# LEDMATRIX.net
KiCad netlist of a schematic drawn in Altium Designer
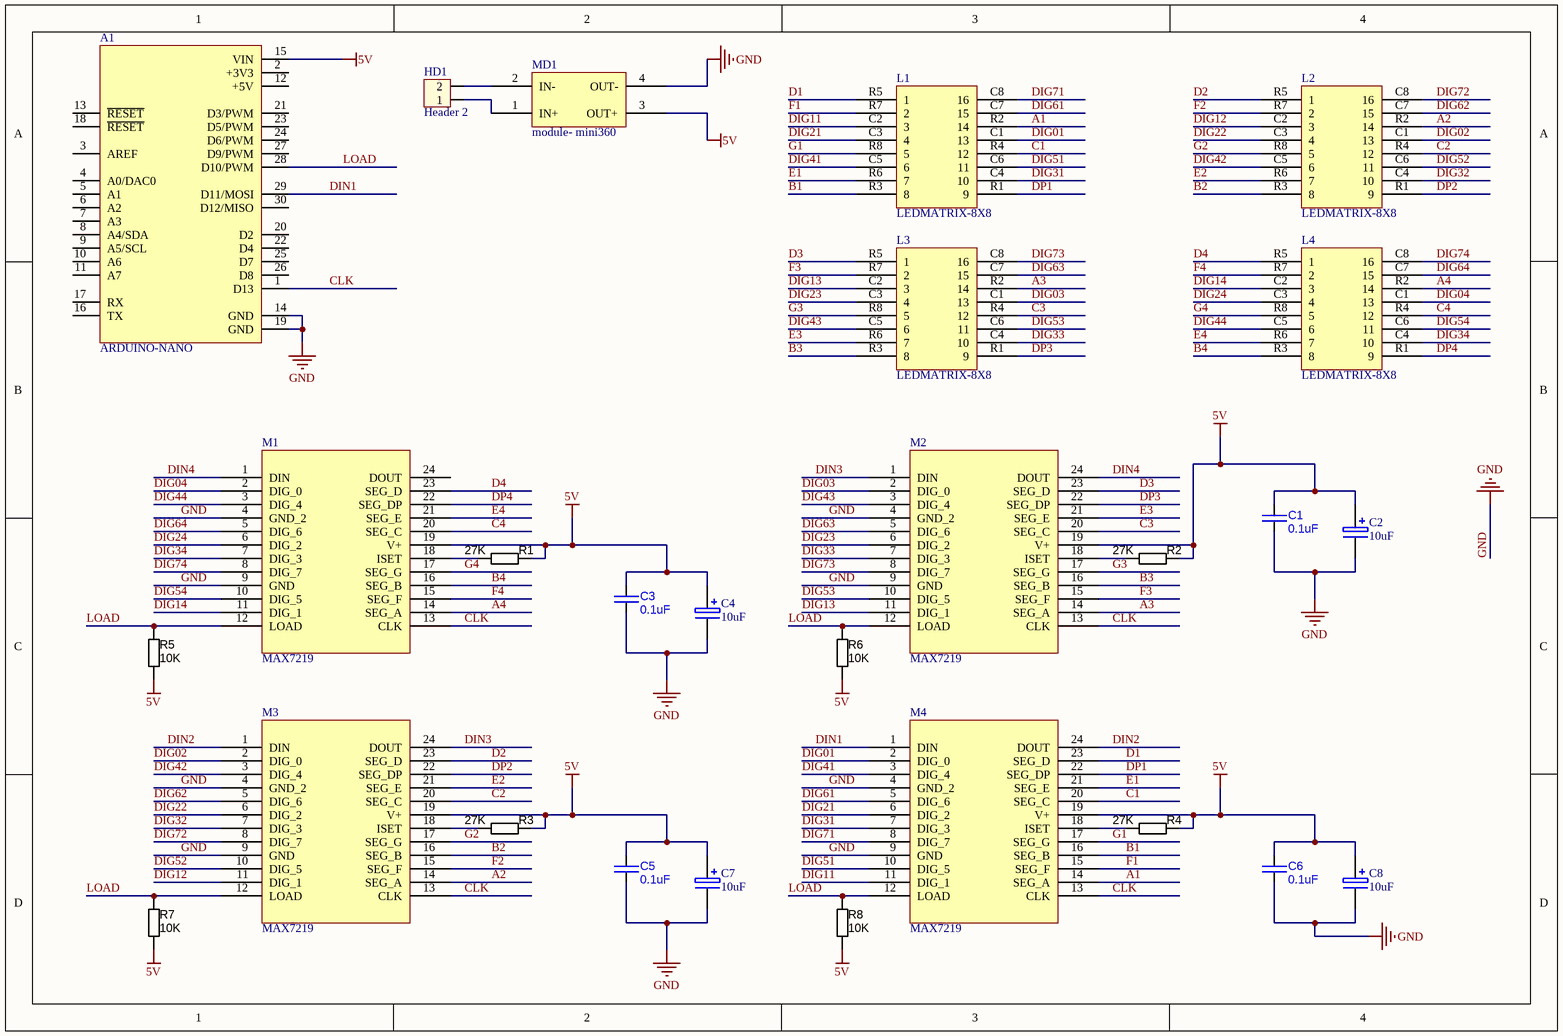
[diagram p0: LEDMATRIX.SchDoc]

(export (version "E")
  (design (tool "Eeschema 10.0.6"))
  (components
    (comp (ref "A1")
      (value "ARDUINO-NANO")
      (footprint "ARDUINO-NANO")
      (libsource (lib "ledmatrix") (part "ARDUINO-NANO"))
    )
    (comp (ref "C1")
      (value "0.1uF")
      (footprint "CAPC2012X135N")
      (description "Capacitor SMD Cer 1.8nF 10% 50V X7R 0805")
      (fields (field (name "TOLERANCE") "±10%") (field (name "Comment") "approved sub OK"))
      (libsource (lib "My library altium") (part "CAP C_0805"))
    )
    (comp (ref "C2")
      (value "10uF")
      (footprint "CP1/2")
      (description "Cap")
      (libsource (lib "My library altium") (part "CAP hoa"))
    )
    (comp (ref "C3")
      (value "0.1uF")
      (footprint "CAPC2012X135N")
      (description "Capacitor SMD Cer 1.8nF 10% 50V X7R 0805")
      (fields (field (name "TOLERANCE") "±10%") (field (name "Comment") "approved sub OK"))
      (libsource (lib "My library altium") (part "CAP C_0805"))
    )
    (comp (ref "C4")
      (value "10uF")
      (footprint "CP1/2")
      (description "Cap")
      (libsource (lib "My library altium") (part "CAP hoa"))
    )
    (comp (ref "C5")
      (value "0.1uF")
      (footprint "CAPC2012X135N")
      (description "Capacitor SMD Cer 1.8nF 10% 50V X7R 0805")
      (fields (field (name "TOLERANCE") "±10%") (field (name "Comment") "approved sub OK"))
      (libsource (lib "My library altium") (part "CAP C_0805"))
    )
    (comp (ref "C6")
      (value "0.1uF")
      (footprint "CAPC2012X135N")
      (description "Capacitor SMD Cer 1.8nF 10% 50V X7R 0805")
      (fields (field (name "TOLERANCE") "±10%") (field (name "Comment") "approved sub OK"))
      (libsource (lib "My library altium") (part "CAP C_0805"))
    )
    (comp (ref "C7")
      (value "10uF")
      (footprint "CP1/2")
      (description "Cap")
      (libsource (lib "My library altium") (part "CAP hoa"))
    )
    (comp (ref "C8")
      (value "10uF")
      (footprint "CP1/2")
      (description "Cap")
      (libsource (lib "My library altium") (part "CAP hoa"))
    )
    (comp (ref "HD1")
      (value "Header 2")
      (footprint "HED2")
      (description "Header 2 (Green)")
      (libsource (lib "My library altium") (part "Header 2"))
    )
    (comp (ref "L1")
      (value "LEDMATRIX-8X8")
      (footprint "LEDMATRIX_8X8")
      (libsource (lib "ledmatrix") (part "LEDMATRIX-8X8"))
    )
    (comp (ref "L2")
      (value "LEDMATRIX-8X8")
      (footprint "LEDMATRIX_8X8")
      (libsource (lib "ledmatrix") (part "LEDMATRIX-8X8"))
    )
    (comp (ref "L3")
      (value "LEDMATRIX-8X8")
      (footprint "LEDMATRIX_8X8")
      (libsource (lib "ledmatrix") (part "LEDMATRIX-8X8"))
    )
    (comp (ref "L4")
      (value "LEDMATRIX-8X8")
      (footprint "LEDMATRIX_8X8")
      (libsource (lib "ledmatrix") (part "LEDMATRIX-8X8"))
    )
    (comp (ref "M1") (value "MAX7219") (footprint "MAX7219") (libsource (lib "ledmatrix") (part "MAX7219")))
    (comp (ref "M2") (value "MAX7219") (footprint "MAX7219") (libsource (lib "ledmatrix") (part "MAX7219")))
    (comp (ref "M3") (value "MAX7219") (footprint "MAX7219") (libsource (lib "ledmatrix") (part "MAX7219")))
    (comp (ref "M4") (value "MAX7219") (footprint "MAX7219") (libsource (lib "ledmatrix") (part "MAX7219")))
    (comp (ref "MD1")
      (value "module- mini360")
      (footprint "MODULE-MINI360")
      (libsource (lib "ledmatrix") (part "module- mini360"))
    )
    (comp (ref "R1")
      (value "27K")
      (footprint "RESC3216N_ZERO")
      (description "Resistor SMD chip 0.0 Ohm 0.25W 1206")
      (fields (field (name "TOLERANCE") "±5%") (field (name "Comment") "Thick Film"))
      (libsource (lib "") (part "RES_1206_1"))
    )
    (comp (ref "R2")
      (value "27K")
      (footprint "RESC3216N_ZERO")
      (description "Resistor SMD chip 0.0 Ohm 0.25W 1206")
      (fields (field (name "TOLERANCE") "±5%") (field (name "Comment") "Thick Film"))
      (libsource (lib "") (part "RES_1206_1"))
    )
    (comp (ref "R3")
      (value "27K")
      (footprint "RESC3216N_ZERO")
      (description "Resistor SMD chip 0.0 Ohm 0.25W 1206")
      (fields (field (name "TOLERANCE") "±5%") (field (name "Comment") "Thick Film"))
      (libsource (lib "") (part "RES_1206_1"))
    )
    (comp (ref "R4")
      (value "27K")
      (footprint "RESC3216N_ZERO")
      (description "Resistor SMD chip 0.0 Ohm 0.25W 1206")
      (fields (field (name "TOLERANCE") "±5%") (field (name "Comment") "Thick Film"))
      (libsource (lib "") (part "RES_1206_1"))
    )
    (comp (ref "R5")
      (value "10K")
      (footprint "RESC3216N_ZERO")
      (description "Resistor SMD chip 0.0 Ohm 0.25W 1206")
      (fields (field (name "TOLERANCE") "±5%") (field (name "Comment") "Thick Film"))
      (libsource (lib "My library altium") (part "RES_1206"))
    )
    (comp (ref "R6")
      (value "10K")
      (footprint "RESC3216N_ZERO")
      (description "Resistor SMD chip 0.0 Ohm 0.25W 1206")
      (fields (field (name "TOLERANCE") "±5%") (field (name "Comment") "Thick Film"))
      (libsource (lib "My library altium") (part "RES_1206"))
    )
    (comp (ref "R7")
      (value "10K")
      (footprint "RESC3216N_ZERO")
      (description "Resistor SMD chip 0.0 Ohm 0.25W 1206")
      (fields (field (name "TOLERANCE") "±5%") (field (name "Comment") "Thick Film"))
      (libsource (lib "My library altium") (part "RES_1206"))
    )
    (comp (ref "R8")
      (value "10K")
      (footprint "RESC3216N_ZERO")
      (description "Resistor SMD chip 0.0 Ohm 0.25W 1206")
      (fields (field (name "TOLERANCE") "±5%") (field (name "Comment") "Thick Film"))
      (libsource (lib "My library altium") (part "RES_1206"))
    )
  )
  (nets
    (net (code "1") (name "/A1") (class "Default")
      (node (ref "L1") (pin "R2") (pinfunction "14_R2") (pintype "passive"))
      (node (ref "M4") (pin "14") (pinfunction "SEG_A_14") (pintype "passive"))
    )
    (net (code "2") (name "/A2") (class "Default")
      (node (ref "L2") (pin "R2") (pinfunction "14_R2") (pintype "passive"))
      (node (ref "M3") (pin "14") (pinfunction "SEG_A_14") (pintype "passive"))
    )
    (net (code "3") (name "/A3") (class "Default")
      (node (ref "L3") (pin "R2") (pinfunction "14_R2") (pintype "passive"))
      (node (ref "M2") (pin "14") (pinfunction "SEG_A_14") (pintype "passive"))
    )
    (net (code "4") (name "/A4") (class "Default")
      (node (ref "L4") (pin "R2") (pinfunction "14_R2") (pintype "passive"))
      (node (ref "M1") (pin "14") (pinfunction "SEG_A_14") (pintype "passive"))
    )
    (net (code "5") (name "/B1") (class "Default")
      (node (ref "L1") (pin "R3") (pinfunction "8_R3") (pintype "passive"))
      (node (ref "M4") (pin "16") (pinfunction "SEG_B_16") (pintype "passive"))
    )
    (net (code "6") (name "/B2") (class "Default")
      (node (ref "L2") (pin "R3") (pinfunction "8_R3") (pintype "passive"))
      (node (ref "M3") (pin "16") (pinfunction "SEG_B_16") (pintype "passive"))
    )
    (net (code "7") (name "/B3") (class "Default")
      (node (ref "L3") (pin "R3") (pinfunction "8_R3") (pintype "passive"))
      (node (ref "M2") (pin "16") (pinfunction "SEG_B_16") (pintype "passive"))
    )
    (net (code "8") (name "/B4") (class "Default")
      (node (ref "L4") (pin "R3") (pinfunction "8_R3") (pintype "passive"))
      (node (ref "M1") (pin "16") (pinfunction "SEG_B_16") (pintype "passive"))
    )
    (net (code "9") (name "/C1") (class "Default")
      (node (ref "L1") (pin "R4") (pinfunction "12_R4") (pintype "passive"))
      (node (ref "M4") (pin "20") (pinfunction "SEG_C_20") (pintype "passive"))
    )
    (net (code "10") (name "/C2") (class "Default")
      (node (ref "L2") (pin "R4") (pinfunction "12_R4") (pintype "passive"))
      (node (ref "M3") (pin "20") (pinfunction "SEG_C_20") (pintype "passive"))
    )
    (net (code "11") (name "/C3") (class "Default")
      (node (ref "L3") (pin "R4") (pinfunction "12_R4") (pintype "passive"))
      (node (ref "M2") (pin "20") (pinfunction "SEG_C_20") (pintype "passive"))
    )
    (net (code "12") (name "/C4") (class "Default")
      (node (ref "L4") (pin "R4") (pinfunction "12_R4") (pintype "passive"))
      (node (ref "M1") (pin "20") (pinfunction "SEG_C_20") (pintype "passive"))
    )
    (net (code "13") (name "/CLK") (class "Default")
      (node (ref "A1") (pin "1") (pinfunction "D13_1") (pintype "passive"))
      (node (ref "M1") (pin "13") (pinfunction "CLK_13") (pintype "passive"))
      (node (ref "M2") (pin "13") (pinfunction "CLK_13") (pintype "passive"))
      (node (ref "M3") (pin "13") (pinfunction "CLK_13") (pintype "passive"))
      (node (ref "M4") (pin "13") (pinfunction "CLK_13") (pintype "passive"))
    )
    (net (code "14") (name "/D1") (class "Default")
      (node (ref "L1") (pin "R5") (pinfunction "1_R5") (pintype "passive"))
      (node (ref "M4") (pin "23") (pinfunction "SEG_D_23") (pintype "passive"))
    )
    (net (code "15") (name "/D2") (class "Default")
      (node (ref "L2") (pin "R5") (pinfunction "1_R5") (pintype "passive"))
      (node (ref "M3") (pin "23") (pinfunction "SEG_D_23") (pintype "passive"))
    )
    (net (code "16") (name "/D3") (class "Default")
      (node (ref "L3") (pin "R5") (pinfunction "1_R5") (pintype "passive"))
      (node (ref "M2") (pin "23") (pinfunction "SEG_D_23") (pintype "passive"))
    )
    (net (code "17") (name "/D4") (class "Default")
      (node (ref "L4") (pin "R5") (pinfunction "1_R5") (pintype "passive"))
      (node (ref "M1") (pin "23") (pinfunction "SEG_D_23") (pintype "passive"))
    )
    (net (code "18") (name "/DIG01") (class "Default")
      (node (ref "L1") (pin "C1") (pinfunction "13_C1") (pintype "passive"))
      (node (ref "M4") (pin "2") (pinfunction "DIG_0_2") (pintype "passive"))
    )
    (net (code "19") (name "/DIG02") (class "Default")
      (node (ref "L2") (pin "C1") (pinfunction "13_C1") (pintype "passive"))
      (node (ref "M3") (pin "2") (pinfunction "DIG_0_2") (pintype "passive"))
    )
    (net (code "20") (name "/DIG03") (class "Default")
      (node (ref "L3") (pin "C1") (pinfunction "13_C1") (pintype "passive"))
      (node (ref "M2") (pin "2") (pinfunction "DIG_0_2") (pintype "passive"))
    )
    (net (code "21") (name "/DIG04") (class "Default")
      (node (ref "L4") (pin "C1") (pinfunction "13_C1") (pintype "passive"))
      (node (ref "M1") (pin "2") (pinfunction "DIG_0_2") (pintype "passive"))
    )
    (net (code "22") (name "/DIG11") (class "Default")
      (node (ref "L1") (pin "C2") (pinfunction "3_C2") (pintype "passive"))
      (node (ref "M4") (pin "11") (pinfunction "DIG_1_11") (pintype "passive"))
    )
    (net (code "23") (name "/DIG12") (class "Default")
      (node (ref "L2") (pin "C2") (pinfunction "3_C2") (pintype "passive"))
      (node (ref "M3") (pin "11") (pinfunction "DIG_1_11") (pintype "passive"))
    )
    (net (code "24") (name "/DIG13") (class "Default")
      (node (ref "L3") (pin "C2") (pinfunction "3_C2") (pintype "passive"))
      (node (ref "M2") (pin "11") (pinfunction "DIG_1_11") (pintype "passive"))
    )
    (net (code "25") (name "/DIG14") (class "Default")
      (node (ref "L4") (pin "C2") (pinfunction "3_C2") (pintype "passive"))
      (node (ref "M1") (pin "11") (pinfunction "DIG_1_11") (pintype "passive"))
    )
    (net (code "26") (name "/DIG21") (class "Default")
      (node (ref "L1") (pin "C3") (pinfunction "4_C3") (pintype "passive"))
      (node (ref "M4") (pin "6") (pinfunction "DIG_2_6") (pintype "passive"))
    )
    (net (code "27") (name "/DIG22") (class "Default")
      (node (ref "L2") (pin "C3") (pinfunction "4_C3") (pintype "passive"))
      (node (ref "M3") (pin "6") (pinfunction "DIG_2_6") (pintype "passive"))
    )
    (net (code "28") (name "/DIG23") (class "Default")
      (node (ref "L3") (pin "C3") (pinfunction "4_C3") (pintype "passive"))
      (node (ref "M2") (pin "6") (pinfunction "DIG_2_6") (pintype "passive"))
    )
    (net (code "29") (name "/DIG24") (class "Default")
      (node (ref "L4") (pin "C3") (pinfunction "4_C3") (pintype "passive"))
      (node (ref "M1") (pin "6") (pinfunction "DIG_2_6") (pintype "passive"))
    )
    (net (code "30") (name "/DIG31") (class "Default")
      (node (ref "L1") (pin "C4") (pinfunction "10_C4") (pintype "passive"))
      (node (ref "M4") (pin "7") (pinfunction "DIG_3_7") (pintype "passive"))
    )
    (net (code "31") (name "/DIG32") (class "Default")
      (node (ref "L2") (pin "C4") (pinfunction "10_C4") (pintype "passive"))
      (node (ref "M3") (pin "7") (pinfunction "DIG_3_7") (pintype "passive"))
    )
    (net (code "32") (name "/DIG33") (class "Default")
      (node (ref "L3") (pin "C4") (pinfunction "10_C4") (pintype "passive"))
      (node (ref "M2") (pin "7") (pinfunction "DIG_3_7") (pintype "passive"))
    )
    (net (code "33") (name "/DIG34") (class "Default")
      (node (ref "L4") (pin "C4") (pinfunction "10_C4") (pintype "passive"))
      (node (ref "M1") (pin "7") (pinfunction "DIG_3_7") (pintype "passive"))
    )
    (net (code "34") (name "/DIG41") (class "Default")
      (node (ref "L1") (pin "C5") (pinfunction "6_C5") (pintype "passive"))
      (node (ref "M4") (pin "3") (pinfunction "DIG_4_3") (pintype "passive"))
    )
    (net (code "35") (name "/DIG42") (class "Default")
      (node (ref "L2") (pin "C5") (pinfunction "6_C5") (pintype "passive"))
      (node (ref "M3") (pin "3") (pinfunction "DIG_4_3") (pintype "passive"))
    )
    (net (code "36") (name "/DIG43") (class "Default")
      (node (ref "L3") (pin "C5") (pinfunction "6_C5") (pintype "passive"))
      (node (ref "M2") (pin "3") (pinfunction "DIG_4_3") (pintype "passive"))
    )
    (net (code "37") (name "/DIG44") (class "Default")
      (node (ref "L4") (pin "C5") (pinfunction "6_C5") (pintype "passive"))
      (node (ref "M1") (pin "3") (pinfunction "DIG_4_3") (pintype "passive"))
    )
    (net (code "38") (name "/DIG51") (class "Default")
      (node (ref "L1") (pin "C6") (pinfunction "11_C6") (pintype "passive"))
      (node (ref "M4") (pin "10") (pinfunction "DIG_5_10") (pintype "passive"))
    )
    (net (code "39") (name "/DIG52") (class "Default")
      (node (ref "L2") (pin "C6") (pinfunction "11_C6") (pintype "passive"))
      (node (ref "M3") (pin "10") (pinfunction "DIG_5_10") (pintype "passive"))
    )
    (net (code "40") (name "/DIG53") (class "Default")
      (node (ref "L3") (pin "C6") (pinfunction "11_C6") (pintype "passive"))
      (node (ref "M2") (pin "10") (pinfunction "DIG_5_10") (pintype "passive"))
    )
    (net (code "41") (name "/DIG54") (class "Default")
      (node (ref "L4") (pin "C6") (pinfunction "11_C6") (pintype "passive"))
      (node (ref "M1") (pin "10") (pinfunction "DIG_5_10") (pintype "passive"))
    )
    (net (code "42") (name "/DIG61") (class "Default")
      (node (ref "L1") (pin "C7") (pinfunction "15_C7") (pintype "passive"))
      (node (ref "M4") (pin "5") (pinfunction "DIG_6_5") (pintype "passive"))
    )
    (net (code "43") (name "/DIG62") (class "Default")
      (node (ref "L2") (pin "C7") (pinfunction "15_C7") (pintype "passive"))
      (node (ref "M3") (pin "5") (pinfunction "DIG_6_5") (pintype "passive"))
    )
    (net (code "44") (name "/DIG63") (class "Default")
      (node (ref "L3") (pin "C7") (pinfunction "15_C7") (pintype "passive"))
      (node (ref "M2") (pin "5") (pinfunction "DIG_6_5") (pintype "passive"))
    )
    (net (code "45") (name "/DIG64") (class "Default")
      (node (ref "L4") (pin "C7") (pinfunction "15_C7") (pintype "passive"))
      (node (ref "M1") (pin "5") (pinfunction "DIG_6_5") (pintype "passive"))
    )
    (net (code "46") (name "/DIG71") (class "Default")
      (node (ref "L1") (pin "C8") (pinfunction "16_C8") (pintype "passive"))
      (node (ref "M4") (pin "8") (pinfunction "DIG_7_8") (pintype "passive"))
    )
    (net (code "47") (name "/DIG72") (class "Default")
      (node (ref "L2") (pin "C8") (pinfunction "16_C8") (pintype "passive"))
      (node (ref "M3") (pin "8") (pinfunction "DIG_7_8") (pintype "passive"))
    )
    (net (code "48") (name "/DIG73") (class "Default")
      (node (ref "L3") (pin "C8") (pinfunction "16_C8") (pintype "passive"))
      (node (ref "M2") (pin "8") (pinfunction "DIG_7_8") (pintype "passive"))
    )
    (net (code "49") (name "/DIG74") (class "Default")
      (node (ref "L4") (pin "C8") (pinfunction "16_C8") (pintype "passive"))
      (node (ref "M1") (pin "8") (pinfunction "DIG_7_8") (pintype "passive"))
    )
    (net (code "50") (name "/DIN1") (class "Default")
      (node (ref "A1") (pin "29") (pinfunction "D11/MOSI_29") (pintype "passive"))
      (node (ref "M4") (pin "1") (pinfunction "DIN_1") (pintype "passive"))
    )
    (net (code "51") (name "/DIN2") (class "Default")
      (node (ref "M3") (pin "1") (pinfunction "DIN_1") (pintype "passive"))
      (node (ref "M4") (pin "24") (pinfunction "DOUT_24") (pintype "passive"))
    )
    (net (code "52") (name "/DIN3") (class "Default")
      (node (ref "M2") (pin "1") (pinfunction "DIN_1") (pintype "passive"))
      (node (ref "M3") (pin "24") (pinfunction "DOUT_24") (pintype "passive"))
    )
    (net (code "53") (name "/DIN4") (class "Default")
      (node (ref "M1") (pin "1") (pinfunction "DIN_1") (pintype "passive"))
      (node (ref "M2") (pin "24") (pinfunction "DOUT_24") (pintype "passive"))
    )
    (net (code "54") (name "/DP1") (class "Default")
      (node (ref "L1") (pin "R1") (pinfunction "9_R1") (pintype "passive"))
      (node (ref "M4") (pin "22") (pinfunction "SEG_DP_22") (pintype "passive"))
    )
    (net (code "55") (name "/DP2") (class "Default")
      (node (ref "L2") (pin "R1") (pinfunction "9_R1") (pintype "passive"))
      (node (ref "M3") (pin "22") (pinfunction "SEG_DP_22") (pintype "passive"))
    )
    (net (code "56") (name "/DP3") (class "Default")
      (node (ref "L3") (pin "R1") (pinfunction "9_R1") (pintype "passive"))
      (node (ref "M2") (pin "22") (pinfunction "SEG_DP_22") (pintype "passive"))
    )
    (net (code "57") (name "/DP4") (class "Default")
      (node (ref "L4") (pin "R1") (pinfunction "9_R1") (pintype "passive"))
      (node (ref "M1") (pin "22") (pinfunction "SEG_DP_22") (pintype "passive"))
    )
    (net (code "58") (name "/E1") (class "Default")
      (node (ref "L1") (pin "R6") (pinfunction "7_R6") (pintype "passive"))
      (node (ref "M4") (pin "21") (pinfunction "SEG_E_21") (pintype "passive"))
    )
    (net (code "59") (name "/E2") (class "Default")
      (node (ref "L2") (pin "R6") (pinfunction "7_R6") (pintype "passive"))
      (node (ref "M3") (pin "21") (pinfunction "SEG_E_21") (pintype "passive"))
    )
    (net (code "60") (name "/E3") (class "Default")
      (node (ref "L3") (pin "R6") (pinfunction "7_R6") (pintype "passive"))
      (node (ref "M2") (pin "21") (pinfunction "SEG_E_21") (pintype "passive"))
    )
    (net (code "61") (name "/E4") (class "Default")
      (node (ref "L4") (pin "R6") (pinfunction "7_R6") (pintype "passive"))
      (node (ref "M1") (pin "21") (pinfunction "SEG_E_21") (pintype "passive"))
    )
    (net (code "62") (name "/F1") (class "Default")
      (node (ref "L1") (pin "R7") (pinfunction "2_R7") (pintype "passive"))
      (node (ref "M4") (pin "15") (pinfunction "SEG_F_15") (pintype "passive"))
    )
    (net (code "63") (name "/F2") (class "Default")
      (node (ref "L2") (pin "R7") (pinfunction "2_R7") (pintype "passive"))
      (node (ref "M3") (pin "15") (pinfunction "SEG_F_15") (pintype "passive"))
    )
    (net (code "64") (name "/F3") (class "Default")
      (node (ref "L3") (pin "R7") (pinfunction "2_R7") (pintype "passive"))
      (node (ref "M2") (pin "15") (pinfunction "SEG_F_15") (pintype "passive"))
    )
    (net (code "65") (name "/F4") (class "Default")
      (node (ref "L4") (pin "R7") (pinfunction "2_R7") (pintype "passive"))
      (node (ref "M1") (pin "15") (pinfunction "SEG_F_15") (pintype "passive"))
    )
    (net (code "66") (name "/G1") (class "Default")
      (node (ref "L1") (pin "R8") (pinfunction "5_R8") (pintype "passive"))
      (node (ref "M4") (pin "17") (pinfunction "SEG_G_17") (pintype "passive"))
    )
    (net (code "67") (name "/G2") (class "Default")
      (node (ref "L2") (pin "R8") (pinfunction "5_R8") (pintype "passive"))
      (node (ref "M3") (pin "17") (pinfunction "SEG_G_17") (pintype "passive"))
    )
    (net (code "68") (name "/G3") (class "Default")
      (node (ref "L3") (pin "R8") (pinfunction "5_R8") (pintype "passive"))
      (node (ref "M2") (pin "17") (pinfunction "SEG_G_17") (pintype "passive"))
    )
    (net (code "69") (name "/G4") (class "Default")
      (node (ref "L4") (pin "R8") (pinfunction "5_R8") (pintype "passive"))
      (node (ref "M1") (pin "17") (pinfunction "SEG_G_17") (pintype "passive"))
    )
    (net (code "70") (name "/LOAD") (class "Default")
      (node (ref "A1") (pin "28") (pinfunction "D10/PWM_28") (pintype "passive"))
      (node (ref "M1") (pin "12") (pinfunction "LOAD_12") (pintype "passive"))
      (node (ref "M2") (pin "12") (pinfunction "LOAD_12") (pintype "passive"))
      (node (ref "M3") (pin "12") (pinfunction "LOAD_12") (pintype "passive"))
      (node (ref "M4") (pin "12") (pinfunction "LOAD_12") (pintype "passive"))
      (node (ref "R5") (pin "1") (pinfunction "1_1") (pintype "passive"))
      (node (ref "R6") (pin "1") (pinfunction "1_1") (pintype "passive"))
      (node (ref "R7") (pin "1") (pinfunction "1_1") (pintype "passive"))
      (node (ref "R8") (pin "1") (pinfunction "1_1") (pintype "passive"))
    )
    (net (code "71") (name "5V") (class "Default")
      (node (ref "A1") (pin "15") (pinfunction "VIN_15") (pintype "passive"))
      (node (ref "C1") (pin "1") (pintype "passive"))
      (node (ref "C2") (pin "1") (pintype "passive"))
      (node (ref "C3") (pin "1") (pintype "passive"))
      (node (ref "C4") (pin "1") (pintype "passive"))
      (node (ref "C5") (pin "1") (pintype "passive"))
      (node (ref "C6") (pin "1") (pintype "passive"))
      (node (ref "C7") (pin "1") (pintype "passive"))
      (node (ref "C8") (pin "1") (pintype "passive"))
      (node (ref "M1") (pin "19") (pinfunction "V+_19") (pintype "power_in"))
      (node (ref "M2") (pin "19") (pinfunction "V+_19") (pintype "power_in"))
      (node (ref "M3") (pin "19") (pinfunction "V+_19") (pintype "power_in"))
      (node (ref "M4") (pin "19") (pinfunction "V+_19") (pintype "power_in"))
      (node (ref "MD1") (pin "3") (pinfunction "OUT+_3") (pintype "passive"))
      (node (ref "R1") (pin "2") (pinfunction "2_2") (pintype "passive"))
      (node (ref "R2") (pin "2") (pinfunction "2_2") (pintype "passive"))
      (node (ref "R3") (pin "2") (pinfunction "2_2") (pintype "passive"))
      (node (ref "R4") (pin "2") (pinfunction "2_2") (pintype "passive"))
      (node (ref "R5") (pin "2") (pinfunction "2_2") (pintype "passive"))
      (node (ref "R6") (pin "2") (pinfunction "2_2") (pintype "passive"))
      (node (ref "R7") (pin "2") (pinfunction "2_2") (pintype "passive"))
      (node (ref "R8") (pin "2") (pinfunction "2_2") (pintype "passive"))
    )
    (net (code "72") (name "GND") (class "Default")
      (node (ref "A1") (pin "14") (pinfunction "GND_14") (pintype "passive"))
      (node (ref "A1") (pin "19") (pinfunction "GND_19") (pintype "passive"))
      (node (ref "C1") (pin "2") (pintype "passive"))
      (node (ref "C2") (pin "2") (pintype "passive"))
      (node (ref "C3") (pin "2") (pintype "passive"))
      (node (ref "C4") (pin "2") (pintype "passive"))
      (node (ref "C5") (pin "2") (pintype "passive"))
      (node (ref "C6") (pin "2") (pintype "passive"))
      (node (ref "C7") (pin "2") (pintype "passive"))
      (node (ref "C8") (pin "2") (pintype "passive"))
      (node (ref "M1") (pin "4") (pinfunction "GND_2_4") (pintype "power_in"))
      (node (ref "M1") (pin "9") (pinfunction "GND_9") (pintype "power_in"))
      (node (ref "M2") (pin "4") (pinfunction "GND_2_4") (pintype "power_in"))
      (node (ref "M2") (pin "9") (pinfunction "GND_9") (pintype "power_in"))
      (node (ref "M3") (pin "4") (pinfunction "GND_2_4") (pintype "power_in"))
      (node (ref "M3") (pin "9") (pinfunction "GND_9") (pintype "power_in"))
      (node (ref "M4") (pin "4") (pinfunction "GND_2_4") (pintype "power_in"))
      (node (ref "M4") (pin "9") (pinfunction "GND_9") (pintype "power_in"))
      (node (ref "MD1") (pin "4") (pinfunction "OUT-_4") (pintype "passive"))
    )
    (net (code "73") (name "Net-(M1-ISET)") (class "Default")
      (node (ref "M1") (pin "18") (pinfunction "ISET_18") (pintype "passive"))
      (node (ref "R1") (pin "1") (pinfunction "1_1") (pintype "passive"))
    )
    (net (code "74") (name "Net-(M2-ISET)") (class "Default")
      (node (ref "M2") (pin "18") (pinfunction "ISET_18") (pintype "passive"))
      (node (ref "R2") (pin "1") (pinfunction "1_1") (pintype "passive"))
    )
    (net (code "75") (name "Net-(M3-ISET)") (class "Default")
      (node (ref "M3") (pin "18") (pinfunction "ISET_18") (pintype "passive"))
      (node (ref "R3") (pin "1") (pinfunction "1_1") (pintype "passive"))
    )
    (net (code "76") (name "Net-(M4-ISET)") (class "Default")
      (node (ref "M4") (pin "18") (pinfunction "ISET_18") (pintype "passive"))
      (node (ref "R4") (pin "1") (pinfunction "1_1") (pintype "passive"))
    )
    (net (code "77") (name "Net-(MD1-IN+)") (class "Default")
      (node (ref "HD1") (pin "1") (pinfunction "1_1") (pintype "passive"))
      (node (ref "MD1") (pin "1") (pinfunction "IN+_1") (pintype "passive"))
    )
    (net (code "78") (name "Net-(MD1-IN-)") (class "Default")
      (node (ref "HD1") (pin "2") (pinfunction "2_2") (pintype "passive"))
      (node (ref "MD1") (pin "2") (pinfunction "IN-_2") (pintype "passive"))
    )
    (net (code "79") (name "unconnected-(A1-+3V3-Pad2)") (class "Default")
      (node (ref "A1") (pin "2") (pinfunction "+3V3_2") (pintype "passive"))
    )
    (net (code "80") (name "unconnected-(A1-+5V-Pad12)") (class "Default")
      (node (ref "A1") (pin "12") (pinfunction "+5V_12") (pintype "passive"))
    )
    (net (code "81") (name "unconnected-(A1-A0{slash}DAC0-Pad4)") (class "Default")
      (node (ref "A1") (pin "4") (pinfunction "A0/DAC0_4") (pintype "passive"))
    )
    (net (code "82") (name "unconnected-(A1-A1-Pad5)") (class "Default")
      (node (ref "A1") (pin "5") (pinfunction "A1_5") (pintype "passive"))
    )
    (net (code "83") (name "unconnected-(A1-A2-Pad6)") (class "Default")
      (node (ref "A1") (pin "6") (pinfunction "A2_6") (pintype "passive"))
    )
    (net (code "84") (name "unconnected-(A1-A3-Pad7)") (class "Default")
      (node (ref "A1") (pin "7") (pinfunction "A3_7") (pintype "passive"))
    )
    (net (code "85") (name "unconnected-(A1-A4{slash}SDA-Pad8)") (class "Default")
      (node (ref "A1") (pin "8") (pinfunction "A4/SDA_8") (pintype "passive"))
    )
    (net (code "86") (name "unconnected-(A1-A5{slash}SCL-Pad9)") (class "Default")
      (node (ref "A1") (pin "9") (pinfunction "A5/SCL_9") (pintype "passive"))
    )
    (net (code "87") (name "unconnected-(A1-A6-Pad10)") (class "Default")
      (node (ref "A1") (pin "10") (pinfunction "A6_10") (pintype "passive"))
    )
    (net (code "88") (name "unconnected-(A1-A7-Pad11)") (class "Default")
      (node (ref "A1") (pin "11") (pinfunction "A7_11") (pintype "passive"))
    )
    (net (code "89") (name "unconnected-(A1-AREF-Pad3)") (class "Default")
      (node (ref "A1") (pin "3") (pinfunction "AREF_3") (pintype "passive"))
    )
    (net (code "90") (name "unconnected-(A1-D2-Pad20)") (class "Default")
      (node (ref "A1") (pin "20") (pinfunction "D2_20") (pintype "passive"))
    )
    (net (code "91") (name "unconnected-(A1-D3{slash}PWM-Pad21)") (class "Default")
      (node (ref "A1") (pin "21") (pinfunction "D3/PWM_21") (pintype "passive"))
    )
    (net (code "92") (name "unconnected-(A1-D4-Pad22)") (class "Default")
      (node (ref "A1") (pin "22") (pinfunction "D4_22") (pintype "passive"))
    )
    (net (code "93") (name "unconnected-(A1-D5{slash}PWM-Pad23)") (class "Default")
      (node (ref "A1") (pin "23") (pinfunction "D5/PWM_23") (pintype "passive"))
    )
    (net (code "94") (name "unconnected-(A1-D6{slash}PWM-Pad24)") (class "Default")
      (node (ref "A1") (pin "24") (pinfunction "D6/PWM_24") (pintype "passive"))
    )
    (net (code "95") (name "unconnected-(A1-D7-Pad25)") (class "Default")
      (node (ref "A1") (pin "25") (pinfunction "D7_25") (pintype "passive"))
    )
    (net (code "96") (name "unconnected-(A1-D8-Pad26)") (class "Default")
      (node (ref "A1") (pin "26") (pinfunction "D8_26") (pintype "passive"))
    )
    (net (code "97") (name "unconnected-(A1-D9{slash}PWM-Pad27)") (class "Default")
      (node (ref "A1") (pin "27") (pinfunction "D9/PWM_27") (pintype "passive"))
    )
    (net (code "98") (name "unconnected-(A1-D12{slash}MISO-Pad30)") (class "Default")
      (node (ref "A1") (pin "30") (pinfunction "D12/MISO_30") (pintype "passive"))
    )
    (net (code "99") (name "unconnected-(A1-RX-Pad17)") (class "Default")
      (node (ref "A1") (pin "17") (pinfunction "RX_17") (pintype "passive"))
    )
    (net (code "100") (name "unconnected-(A1-TX-Pad16)") (class "Default")
      (node (ref "A1") (pin "16") (pinfunction "TX_16") (pintype "passive"))
    )
    (net (code "101") (name "unconnected-(A1-~{RESET}-Pad13)") (class "Default")
      (node (ref "A1") (pin "13") (pinfunction "~{RESET}_13") (pintype "passive"))
    )
    (net (code "102") (name "unconnected-(A1-~{RESET}-Pad18)") (class "Default")
      (node (ref "A1") (pin "18") (pinfunction "~{RESET}_18") (pintype "passive"))
    )
    (net (code "103") (name "unconnected-(M1-DOUT-Pad24)") (class "Default")
      (node (ref "M1") (pin "24") (pinfunction "DOUT_24") (pintype "passive"))
    )
  )
)
